# LLY.net
KiCad netlist of a schematic drawn in Altium Designer
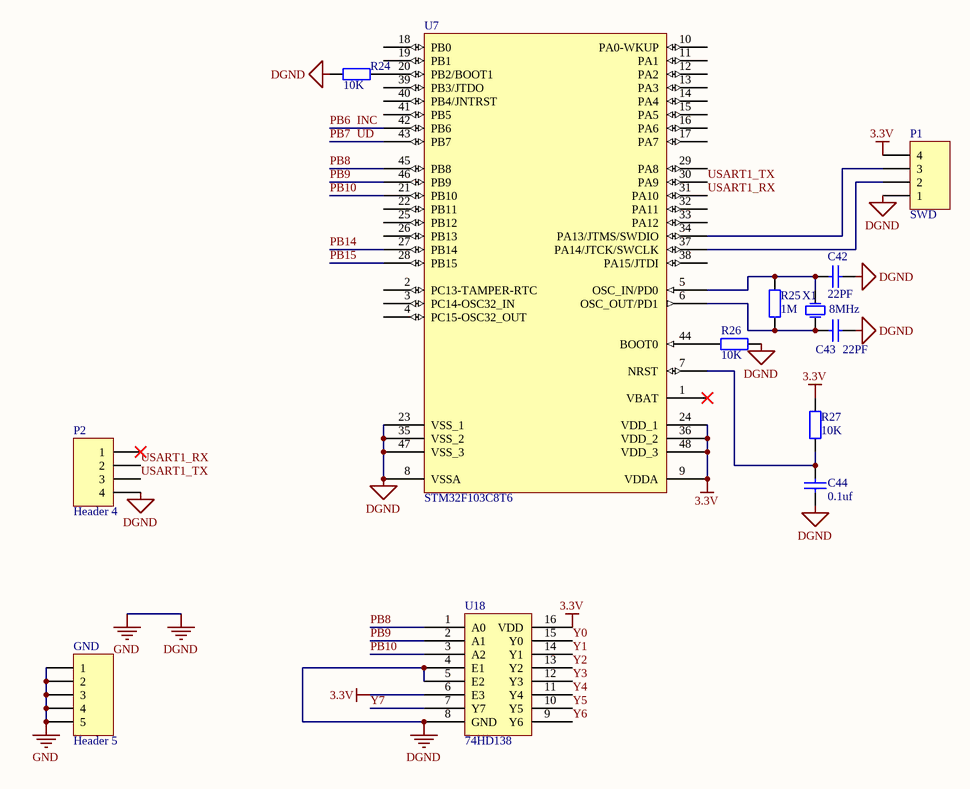
[diagram p0: LLY.SchDoc]

(export (version "E")
  (design (tool "Eeschema 10.0.6"))
  (components
    (comp (ref "C42")
      (value "22PF")
      (footprint "0805C")
      (description "Capacitor")
      (fields (field (name "PUBLISHER") "Altium Limited"))
      (libsource (lib "Miscellaneous Devices") (part "Cap"))
    )
    (comp (ref "C43")
      (value "22PF")
      (footprint "0805C")
      (description "Capacitor")
      (fields (field (name "PUBLISHER") "Altium Limited"))
      (libsource (lib "Miscellaneous Devices") (part "Cap"))
    )
    (comp (ref "C44")
      (value "0.1uf")
      (footprint "0805C")
      (description "Capacitor")
      (fields (field (name "PUBLISHER") "Altium Limited"))
      (libsource (lib "Miscellaneous Devices") (part "Cap"))
    )
    (comp (ref "GND")
      (value "Header 5")
      (footprint "HDR1X5")
      (description "Header, 5-Pin")
      (fields (field (name "PUBLISHER") "Altium Limited"))
      (libsource (lib "Miscellaneous Connectors") (part "Header 5"))
    )
    (comp (ref "P1")
      (value "SWD")
      (footprint "HDR1X4")
      (fields (field (name "PUBLISHER") "Altium Limited"))
      (libsource (lib "Miscellaneous Connectors") (part "Header 4"))
    )
    (comp (ref "P2")
      (value "Header 4")
      (footprint "XH2.54W-4P")
      (description "Header, 4-Pin")
      (fields (field (name "PUBLISHER") "Altium Limited"))
      (libsource (lib "") (part "Header 4_1"))
    )
    (comp (ref "R24")
      (value "10K")
      (footprint "0805R")
      (description "Resistor")
      (fields (field (name "PUBLISHER") "Altium Limited"))
      (libsource (lib "") (part "Res2_1"))
    )
    (comp (ref "R25")
      (value "1M")
      (footprint "0805R")
      (description "Resistor")
      (fields (field (name "PUBLISHER") "Altium Limited"))
      (libsource (lib "") (part "Res2_2"))
    )
    (comp (ref "R26")
      (value "10K")
      (footprint "0805R")
      (description "Resistor")
      (fields (field (name "PUBLISHER") "Altium Limited"))
      (libsource (lib "") (part "Res2_1"))
    )
    (comp (ref "R27")
      (value "10K")
      (footprint "0805R")
      (description "Resistor")
      (fields (field (name "PUBLISHER") "Altium Limited"))
      (libsource (lib "Miscellaneous Devices") (part "Res2"))
    )
    (comp (ref "U7")
      (value "STM32F103C8T6")
      (footprint "LQFP48_L")
      (description "STM32单片机48脚")
      (fields (field (name "PUBLISHER") "Altium Limited"))
      (libsource (lib "ST Microcontroller 32-Bit STM32") (part "STM32F103CBT6"))
    )
    (comp (ref "U18")
      (value "74HD138")
      (footprint "SOP16")
      (description "74HC138")
      (libsource (lib "LLY") (part "74HD138"))
    )
    (comp (ref "X1")
      (value "8MHz")
      (footprint "XTAL_US")
      (description "Crystal Oscillator")
      (fields (field (name "PUBLISHER") "Altium Limited"))
      (libsource (lib "ATK-VS1053 MP3") (part "XTAL"))
    )
  )
  (nets
    (net (code "1") (name "/INC") (class "Default")
      (node (ref "U7") (pin "42") (pinfunction "PB6_42") (pintype "bidirectional"))
    )
    (net (code "2") (name "/PB7") (class "Default")
      (node (ref "U7") (pin "43") (pinfunction "PB7_43") (pintype "bidirectional"))
    )
    (net (code "3") (name "/PB8") (class "Default")
      (node (ref "U18") (pin "1") (pinfunction "A0_1") (pintype "passive"))
      (node (ref "U7") (pin "45") (pinfunction "PB8_45") (pintype "bidirectional"))
    )
    (net (code "4") (name "/PB9") (class "Default")
      (node (ref "U18") (pin "2") (pinfunction "A1_2") (pintype "passive"))
      (node (ref "U7") (pin "46") (pinfunction "PB9_46") (pintype "bidirectional"))
    )
    (net (code "5") (name "/PB10") (class "Default")
      (node (ref "U18") (pin "3") (pinfunction "A2_3") (pintype "passive"))
      (node (ref "U7") (pin "21") (pinfunction "PB10_21") (pintype "bidirectional"))
    )
    (net (code "6") (name "/PB14") (class "Default")
      (node (ref "U7") (pin "27") (pinfunction "PB14_27") (pintype "bidirectional"))
    )
    (net (code "7") (name "/PB15") (class "Default")
      (node (ref "U7") (pin "28") (pinfunction "PB15_28") (pintype "bidirectional"))
    )
    (net (code "8") (name "/USART1_RX") (class "Default")
      (node (ref "P2") (pin "2") (pinfunction "2_2") (pintype "passive"))
      (node (ref "U7") (pin "31") (pinfunction "PA10_31") (pintype "bidirectional"))
    )
    (net (code "9") (name "/USART1_TX") (class "Default")
      (node (ref "P2") (pin "3") (pinfunction "3_3") (pintype "passive"))
      (node (ref "U7") (pin "30") (pinfunction "PA9_30") (pintype "bidirectional"))
    )
    (net (code "10") (name "/Y0") (class "Default")
      (node (ref "U18") (pin "15") (pinfunction "Y0_15") (pintype "passive"))
    )
    (net (code "11") (name "/Y1") (class "Default")
      (node (ref "U18") (pin "14") (pinfunction "Y1_14") (pintype "passive"))
    )
    (net (code "12") (name "/Y2") (class "Default")
      (node (ref "U18") (pin "13") (pinfunction "Y2_13") (pintype "passive"))
    )
    (net (code "13") (name "/Y3") (class "Default")
      (node (ref "U18") (pin "12") (pinfunction "Y3_12") (pintype "passive"))
    )
    (net (code "14") (name "/Y4") (class "Default")
      (node (ref "U18") (pin "11") (pinfunction "Y4_11") (pintype "passive"))
    )
    (net (code "15") (name "/Y5") (class "Default")
      (node (ref "U18") (pin "10") (pinfunction "Y5_10") (pintype "passive"))
    )
    (net (code "16") (name "/Y6") (class "Default")
      (node (ref "U18") (pin "9") (pinfunction "Y6_9") (pintype "passive"))
    )
    (net (code "17") (name "/Y7") (class "Default")
      (node (ref "U18") (pin "7") (pinfunction "Y7_7") (pintype "passive"))
    )
    (net (code "18") (name "3.3V") (class "Default")
      (node (ref "P1") (pin "4") (pinfunction "4_4") (pintype "passive"))
      (node (ref "R27") (pin "2") (pinfunction "2_2") (pintype "passive"))
      (node (ref "U18") (pin "16") (pinfunction "VDD_16") (pintype "passive"))
      (node (ref "U18") (pin "6") (pinfunction "E3_6") (pintype "passive"))
      (node (ref "U7") (pin "24") (pinfunction "VDD_1_24") (pintype "power_in"))
      (node (ref "U7") (pin "36") (pinfunction "VDD_2_36") (pintype "power_in"))
      (node (ref "U7") (pin "48") (pinfunction "VDD_3_48") (pintype "power_in"))
      (node (ref "U7") (pin "9") (pinfunction "VDDA_9") (pintype "power_in"))
    )
    (net (code "19") (name "DGND") (class "Default")
      (node (ref "C42") (pin "1") (pinfunction "1_1") (pintype "passive"))
      (node (ref "C43") (pin "1") (pinfunction "1_1") (pintype "passive"))
      (node (ref "C44") (pin "2") (pinfunction "2_2") (pintype "passive"))
      (node (ref "GND") (pin "1") (pinfunction "1_1") (pintype "passive"))
      (node (ref "GND") (pin "2") (pinfunction "2_2") (pintype "passive"))
      (node (ref "GND") (pin "3") (pinfunction "3_3") (pintype "passive"))
      (node (ref "GND") (pin "4") (pinfunction "4_4") (pintype "passive"))
      (node (ref "GND") (pin "5") (pinfunction "5_5") (pintype "passive"))
      (node (ref "P1") (pin "1") (pinfunction "1_1") (pintype "passive"))
      (node (ref "P2") (pin "4") (pinfunction "4_4") (pintype "passive"))
      (node (ref "R24") (pin "1") (pinfunction "1_1") (pintype "passive"))
      (node (ref "R26") (pin "2") (pinfunction "2_2") (pintype "passive"))
      (node (ref "U18") (pin "4") (pinfunction "E1_4") (pintype "passive"))
      (node (ref "U18") (pin "5") (pinfunction "E2_5") (pintype "passive"))
      (node (ref "U18") (pin "8") (pinfunction "GND_8") (pintype "passive"))
      (node (ref "U7") (pin "23") (pinfunction "VSS_1_23") (pintype "power_in"))
      (node (ref "U7") (pin "35") (pinfunction "VSS_2_35") (pintype "power_in"))
      (node (ref "U7") (pin "47") (pinfunction "VSS_3_47") (pintype "power_in"))
      (node (ref "U7") (pin "8") (pinfunction "VSSA_8") (pintype "power_in"))
    )
    (net (code "20") (name "Net-(U7-BOOT0)") (class "Default")
      (node (ref "R26") (pin "1") (pinfunction "1_1") (pintype "passive"))
      (node (ref "U7") (pin "44") (pinfunction "BOOT0_44") (pintype "input"))
    )
    (net (code "21") (name "Net-(U7-NRST)") (class "Default")
      (node (ref "C44") (pin "1") (pinfunction "1_1") (pintype "passive"))
      (node (ref "R27") (pin "1") (pinfunction "1_1") (pintype "passive"))
      (node (ref "U7") (pin "7") (pinfunction "NRST_7") (pintype "bidirectional"))
    )
    (net (code "22") (name "Net-(U7-OSC_IN{slash}PD0)") (class "Default")
      (node (ref "C42") (pin "2") (pinfunction "2_2") (pintype "passive"))
      (node (ref "R25") (pin "1") (pinfunction "1_1") (pintype "passive"))
      (node (ref "U7") (pin "5") (pinfunction "OSC_IN/PD0_5") (pintype "input"))
      (node (ref "X1") (pin "2") (pinfunction "OSC2_2") (pintype "passive"))
    )
    (net (code "23") (name "Net-(U7-OSC_OUT{slash}PD1)") (class "Default")
      (node (ref "C43") (pin "2") (pinfunction "2_2") (pintype "passive"))
      (node (ref "R25") (pin "2") (pinfunction "2_2") (pintype "passive"))
      (node (ref "U7") (pin "6") (pinfunction "OSC_OUT/PD1_6") (pintype "output"))
      (node (ref "X1") (pin "1") (pinfunction "OSC1_1") (pintype "passive"))
    )
    (net (code "24") (name "Net-(U7-PA13{slash}JTMS{slash}SWDIO)") (class "Default")
      (node (ref "P1") (pin "3") (pinfunction "3_3") (pintype "passive"))
      (node (ref "U7") (pin "34") (pinfunction "PA13/JTMS/SWDIO_34") (pintype "bidirectional"))
    )
    (net (code "25") (name "Net-(U7-PA14{slash}JTCK{slash}SWCLK)") (class "Default")
      (node (ref "P1") (pin "2") (pinfunction "2_2") (pintype "passive"))
      (node (ref "U7") (pin "37") (pinfunction "PA14/JTCK/SWCLK_37") (pintype "bidirectional"))
    )
    (net (code "26") (name "Net-(U7-PB2{slash}BOOT1)") (class "Default")
      (node (ref "R24") (pin "2") (pinfunction "2_2") (pintype "passive"))
      (node (ref "U7") (pin "20") (pinfunction "PB2/BOOT1_20") (pintype "bidirectional"))
    )
    (net (code "27") (name "unconnected-(P2-Pad1)") (class "Default")
      (node (ref "P2") (pin "1") (pinfunction "1_1") (pintype "passive+no_connect"))
    )
    (net (code "28") (name "unconnected-(U7-PA0-WKUP-Pad10)") (class "Default")
      (node (ref "U7") (pin "10") (pinfunction "PA0-WKUP_10") (pintype "bidirectional"))
    )
    (net (code "29") (name "unconnected-(U7-PA1-Pad11)") (class "Default")
      (node (ref "U7") (pin "11") (pinfunction "PA1_11") (pintype "bidirectional"))
    )
    (net (code "30") (name "unconnected-(U7-PA2-Pad12)") (class "Default")
      (node (ref "U7") (pin "12") (pinfunction "PA2_12") (pintype "bidirectional"))
    )
    (net (code "31") (name "unconnected-(U7-PA3-Pad13)") (class "Default")
      (node (ref "U7") (pin "13") (pinfunction "PA3_13") (pintype "bidirectional"))
    )
    (net (code "32") (name "unconnected-(U7-PA4-Pad14)") (class "Default")
      (node (ref "U7") (pin "14") (pinfunction "PA4_14") (pintype "bidirectional"))
    )
    (net (code "33") (name "unconnected-(U7-PA5-Pad15)") (class "Default")
      (node (ref "U7") (pin "15") (pinfunction "PA5_15") (pintype "bidirectional"))
    )
    (net (code "34") (name "unconnected-(U7-PA6-Pad16)") (class "Default")
      (node (ref "U7") (pin "16") (pinfunction "PA6_16") (pintype "bidirectional"))
    )
    (net (code "35") (name "unconnected-(U7-PA7-Pad17)") (class "Default")
      (node (ref "U7") (pin "17") (pinfunction "PA7_17") (pintype "bidirectional"))
    )
    (net (code "36") (name "unconnected-(U7-PA8-Pad29)") (class "Default")
      (node (ref "U7") (pin "29") (pinfunction "PA8_29") (pintype "bidirectional"))
    )
    (net (code "37") (name "unconnected-(U7-PA11-Pad32)") (class "Default")
      (node (ref "U7") (pin "32") (pinfunction "PA11_32") (pintype "bidirectional"))
    )
    (net (code "38") (name "unconnected-(U7-PA12-Pad33)") (class "Default")
      (node (ref "U7") (pin "33") (pinfunction "PA12_33") (pintype "bidirectional"))
    )
    (net (code "39") (name "unconnected-(U7-PA15{slash}JTDI-Pad38)") (class "Default")
      (node (ref "U7") (pin "38") (pinfunction "PA15/JTDI_38") (pintype "bidirectional"))
    )
    (net (code "40") (name "unconnected-(U7-PB0-Pad18)") (class "Default")
      (node (ref "U7") (pin "18") (pinfunction "PB0_18") (pintype "bidirectional"))
    )
    (net (code "41") (name "unconnected-(U7-PB1-Pad19)") (class "Default")
      (node (ref "U7") (pin "19") (pinfunction "PB1_19") (pintype "bidirectional"))
    )
    (net (code "42") (name "unconnected-(U7-PB3{slash}JTDO-Pad39)") (class "Default")
      (node (ref "U7") (pin "39") (pinfunction "PB3/JTDO_39") (pintype "bidirectional"))
    )
    (net (code "43") (name "unconnected-(U7-PB4{slash}JNTRST-Pad40)") (class "Default")
      (node (ref "U7") (pin "40") (pinfunction "PB4/JNTRST_40") (pintype "bidirectional"))
    )
    (net (code "44") (name "unconnected-(U7-PB5-Pad41)") (class "Default")
      (node (ref "U7") (pin "41") (pinfunction "PB5_41") (pintype "bidirectional"))
    )
    (net (code "45") (name "unconnected-(U7-PB11-Pad22)") (class "Default")
      (node (ref "U7") (pin "22") (pinfunction "PB11_22") (pintype "bidirectional"))
    )
    (net (code "46") (name "unconnected-(U7-PB12-Pad25)") (class "Default")
      (node (ref "U7") (pin "25") (pinfunction "PB12_25") (pintype "bidirectional"))
    )
    (net (code "47") (name "unconnected-(U7-PB13-Pad26)") (class "Default")
      (node (ref "U7") (pin "26") (pinfunction "PB13_26") (pintype "bidirectional"))
    )
    (net (code "48") (name "unconnected-(U7-PC13-TAMPER-RTC-Pad2)") (class "Default")
      (node (ref "U7") (pin "2") (pinfunction "PC13-TAMPER-RTC_2") (pintype "bidirectional"))
    )
    (net (code "49") (name "unconnected-(U7-PC14-OSC32_IN-Pad3)") (class "Default")
      (node (ref "U7") (pin "3") (pinfunction "PC14-OSC32_IN_3") (pintype "bidirectional"))
    )
    (net (code "50") (name "unconnected-(U7-PC15-OSC32_OUT-Pad4)") (class "Default")
      (node (ref "U7") (pin "4") (pinfunction "PC15-OSC32_OUT_4") (pintype "bidirectional"))
    )
    (net (code "51") (name "unconnected-(U7-VBAT-Pad1)") (class "Default")
      (node (ref "U7") (pin "1") (pinfunction "VBAT_1") (pintype "power_in+no_connect"))
    )
  )
)
